# Ref_2V5_LM4132AMF.net
KiCad netlist of a schematic drawn in Altium Designer
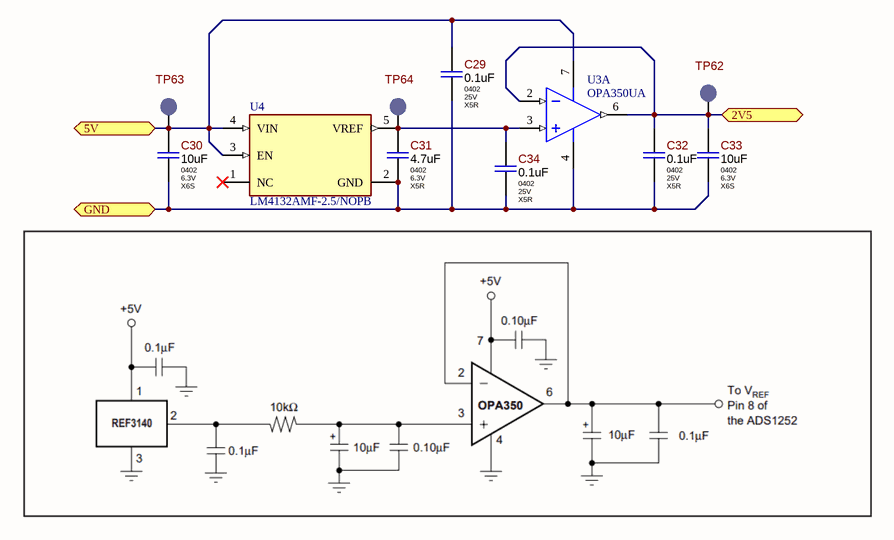
[diagram p0: Ref_2V5_LM4132AMF.SchDoc]

(export (version "E")
  (design (tool "Eeschema 10.0.6"))
  (components
    (comp (ref "C29")
      (value "0.1uF")
      (footprint "C_CERAMIC_0402_MED")
      (description "100nF 25V X5R ±10% 0402 Ceramic Capacitor RoHS")
      (fields
        (field (name "PACKAGE") "0402")
        (field (name "VOLTAGE") "25V")
        (field (name "DIELECTRIC TYPE") "X5R")
        (field (name "PART NUMBER") "CL05A104KA5NNNC")
        (field (name "MANUFACTURER") "Samsung Electro-Mechanics")
      )
      (libsource (lib "EL.XXX.T01") (part "Capacitor-NonPolar"))
    )
    (comp (ref "C30")
      (value "10uF")
      (footprint "C_CERAMIC_0402_MED")
      (description "10uF 6.3V X6S ±20% 0402 Ceramic Capacitor RoHS")
      (fields
        (field (name "PACKAGE") "0402")
        (field (name "VOLTAGE") "6.3V")
        (field (name "DIELECTRIC TYPE") "X6S")
        (field (name "PART NUMBER") "GRM155C80J106ME11D")
        (field (name "MANUFACTURER") "Murata Electronics")
      )
      (libsource (lib "EL.XXX.T01") (part "Capacitor-NonPolar"))
    )
    (comp (ref "C31")
      (value "4.7uF")
      (footprint "C_CERAMIC_0402_MED")
      (description "4.7uF 6.3V X5R ±20% 0402 Ceramic Capacitor RoHS")
      (fields
        (field (name "PACKAGE") "0402")
        (field (name "VOLTAGE") "6.3V")
        (field (name "DIELECTRIC TYPE") "X5R")
        (field (name "PART NUMBER") "GRM155R60J475ME47")
        (field (name "MANUFACTURER") "Murata Electronics")
      )
      (libsource (lib "EL.XXX.T01") (part "Capacitor-NonPolar"))
    )
    (comp (ref "C32")
      (value "0.1uF")
      (footprint "C_CERAMIC_0402_MED")
      (description "100nF 25V X5R ±10% 0402 Ceramic Capacitor RoHS")
      (fields
        (field (name "PACKAGE") "0402")
        (field (name "VOLTAGE") "25V")
        (field (name "DIELECTRIC TYPE") "X5R")
        (field (name "PART NUMBER") "CL05A104KA5NNNC")
        (field (name "MANUFACTURER") "Samsung Electro-Mechanics")
      )
      (libsource (lib "EL.XXX.T01") (part "Capacitor-NonPolar"))
    )
    (comp (ref "C33")
      (value "10uF")
      (footprint "C_CERAMIC_0402_MED")
      (description "10uF 6.3V X6S ±20% 0402 Ceramic Capacitor RoHS")
      (fields
        (field (name "PACKAGE") "0402")
        (field (name "VOLTAGE") "6.3V")
        (field (name "DIELECTRIC TYPE") "X6S")
        (field (name "PART NUMBER") "GRM155C80J106ME11D")
        (field (name "MANUFACTURER") "Murata Electronics")
      )
      (libsource (lib "EL.XXX.T01") (part "Capacitor-NonPolar"))
    )
    (comp (ref "C34")
      (value "0.1uF")
      (footprint "C_CERAMIC_0402_MED")
      (description "100nF 25V X5R ±10% 0402 Ceramic Capacitor RoHS")
      (fields
        (field (name "PACKAGE") "0402")
        (field (name "VOLTAGE") "25V")
        (field (name "DIELECTRIC TYPE") "X5R")
        (field (name "PART NUMBER") "CL05A104KA5NNNC")
        (field (name "MANUFACTURER") "Samsung Electro-Mechanics")
      )
      (libsource (lib "EL.XXX.T01") (part "Capacitor-NonPolar"))
    )
    (comp (ref "TP62")
      (value "LED_LINK")
      (footprint "TP_SMD_2mm")
      (description "Test Point SMD Pad 1.0mm/1.5mm/2mm")
      (fields (field (name "PART NUMBER") "TP-PAD-SMD"))
      (libsource (lib "EL.XXX.T01") (part "Test-Point-SMD-1"))
    )
    (comp (ref "TP63")
      (value "LED_LINK")
      (footprint "TP_SMD_2mm")
      (description "Test Point SMD Pad 1.0mm/1.5mm/2mm")
      (fields (field (name "PART NUMBER") "TP-PAD-SMD"))
      (libsource (lib "EL.XXX.T01") (part "Test-Point-SMD-1"))
    )
    (comp (ref "TP64")
      (value "LED_LINK")
      (footprint "TP_SMD_2mm")
      (description "Test Point SMD Pad 1.0mm/1.5mm/2mm")
      (fields (field (name "PART NUMBER") "TP-PAD-SMD"))
      (libsource (lib "EL.XXX.T01") (part "Test-Point-SMD-1"))
    )
    (comp (ref "U3")
      (value "OPA350UA")
      (footprint "D0008A_M")
      (fields (field (name "MANUFACTURER") "Texas Instruments"))
      (libsource (lib "EL.XXX.T01") (part "TI-OPA-8_1"))
    )
    (comp (ref "U4")
      (value "LM4132AMF-2.5/NOPB")
      (footprint "FP-DBV0005A-IPC_C")
      (description "IC VREF SERIES 0.05% SOT23-5")
      (fields (field (name "TOLERANCE") "0.05%"))
      (libsource (lib "EL.XXX.T01") (part "83a8c20666b8818ecf60699c622df6d"))
    )
  )
  (nets
    (net (code "1") (name "/2V5") (class "Default")
      (node (ref "C32") (pin "1") (pinfunction "1_1") (pintype "passive"))
      (node (ref "C33") (pin "1") (pinfunction "1_1") (pintype "passive"))
      (node (ref "TP62") (pin "1") (pintype "passive"))
      (node (ref "U3") (pin "2") (pinfunction "IN-_2") (pintype "input"))
      (node (ref "U3") (pin "6") (pinfunction "OUT_6") (pintype "output"))
    )
    (net (code "2") (name "/5V") (class "Default")
      (node (ref "C29") (pin "1") (pinfunction "1_1") (pintype "passive"))
      (node (ref "C30") (pin "1") (pinfunction "1_1") (pintype "passive"))
      (node (ref "TP63") (pin "1") (pintype "passive"))
      (node (ref "U3") (pin "7") (pinfunction "V+_7") (pintype "power_in"))
      (node (ref "U4") (pin "3") (pinfunction "EN_3") (pintype "input"))
      (node (ref "U4") (pin "4") (pinfunction "VIN_4") (pintype "input"))
    )
    (net (code "3") (name "/GND") (class "Default")
      (node (ref "C29") (pin "2") (pinfunction "2_2") (pintype "passive"))
      (node (ref "C30") (pin "2") (pinfunction "2_2") (pintype "passive"))
      (node (ref "C31") (pin "2") (pinfunction "2_2") (pintype "passive"))
      (node (ref "C32") (pin "2") (pinfunction "2_2") (pintype "passive"))
      (node (ref "C33") (pin "2") (pinfunction "2_2") (pintype "passive"))
      (node (ref "C34") (pin "2") (pinfunction "2_2") (pintype "passive"))
      (node (ref "U3") (pin "4") (pinfunction "V-_4") (pintype "power_in"))
      (node (ref "U4") (pin "2") (pinfunction "GND_2") (pintype "power_in"))
    )
    (net (code "4") (name "Net-(U3A-IN+)") (class "Default")
      (node (ref "C31") (pin "1") (pinfunction "1_1") (pintype "passive"))
      (node (ref "C34") (pin "1") (pinfunction "1_1") (pintype "passive"))
      (node (ref "TP64") (pin "1") (pintype "passive"))
      (node (ref "U3") (pin "3") (pinfunction "IN+_3") (pintype "input"))
      (node (ref "U4") (pin "5") (pinfunction "VREF_5") (pintype "output"))
    )
    (net (code "5") (name "unconnected-(U4-NC-Pad1)") (class "Default")
      (node (ref "U4") (pin "1") (pinfunction "NC_1") (pintype "passive+no_connect"))
    )
  )
)
